# stack_4.net
KiCad netlist of a schematic drawn in EAGLE
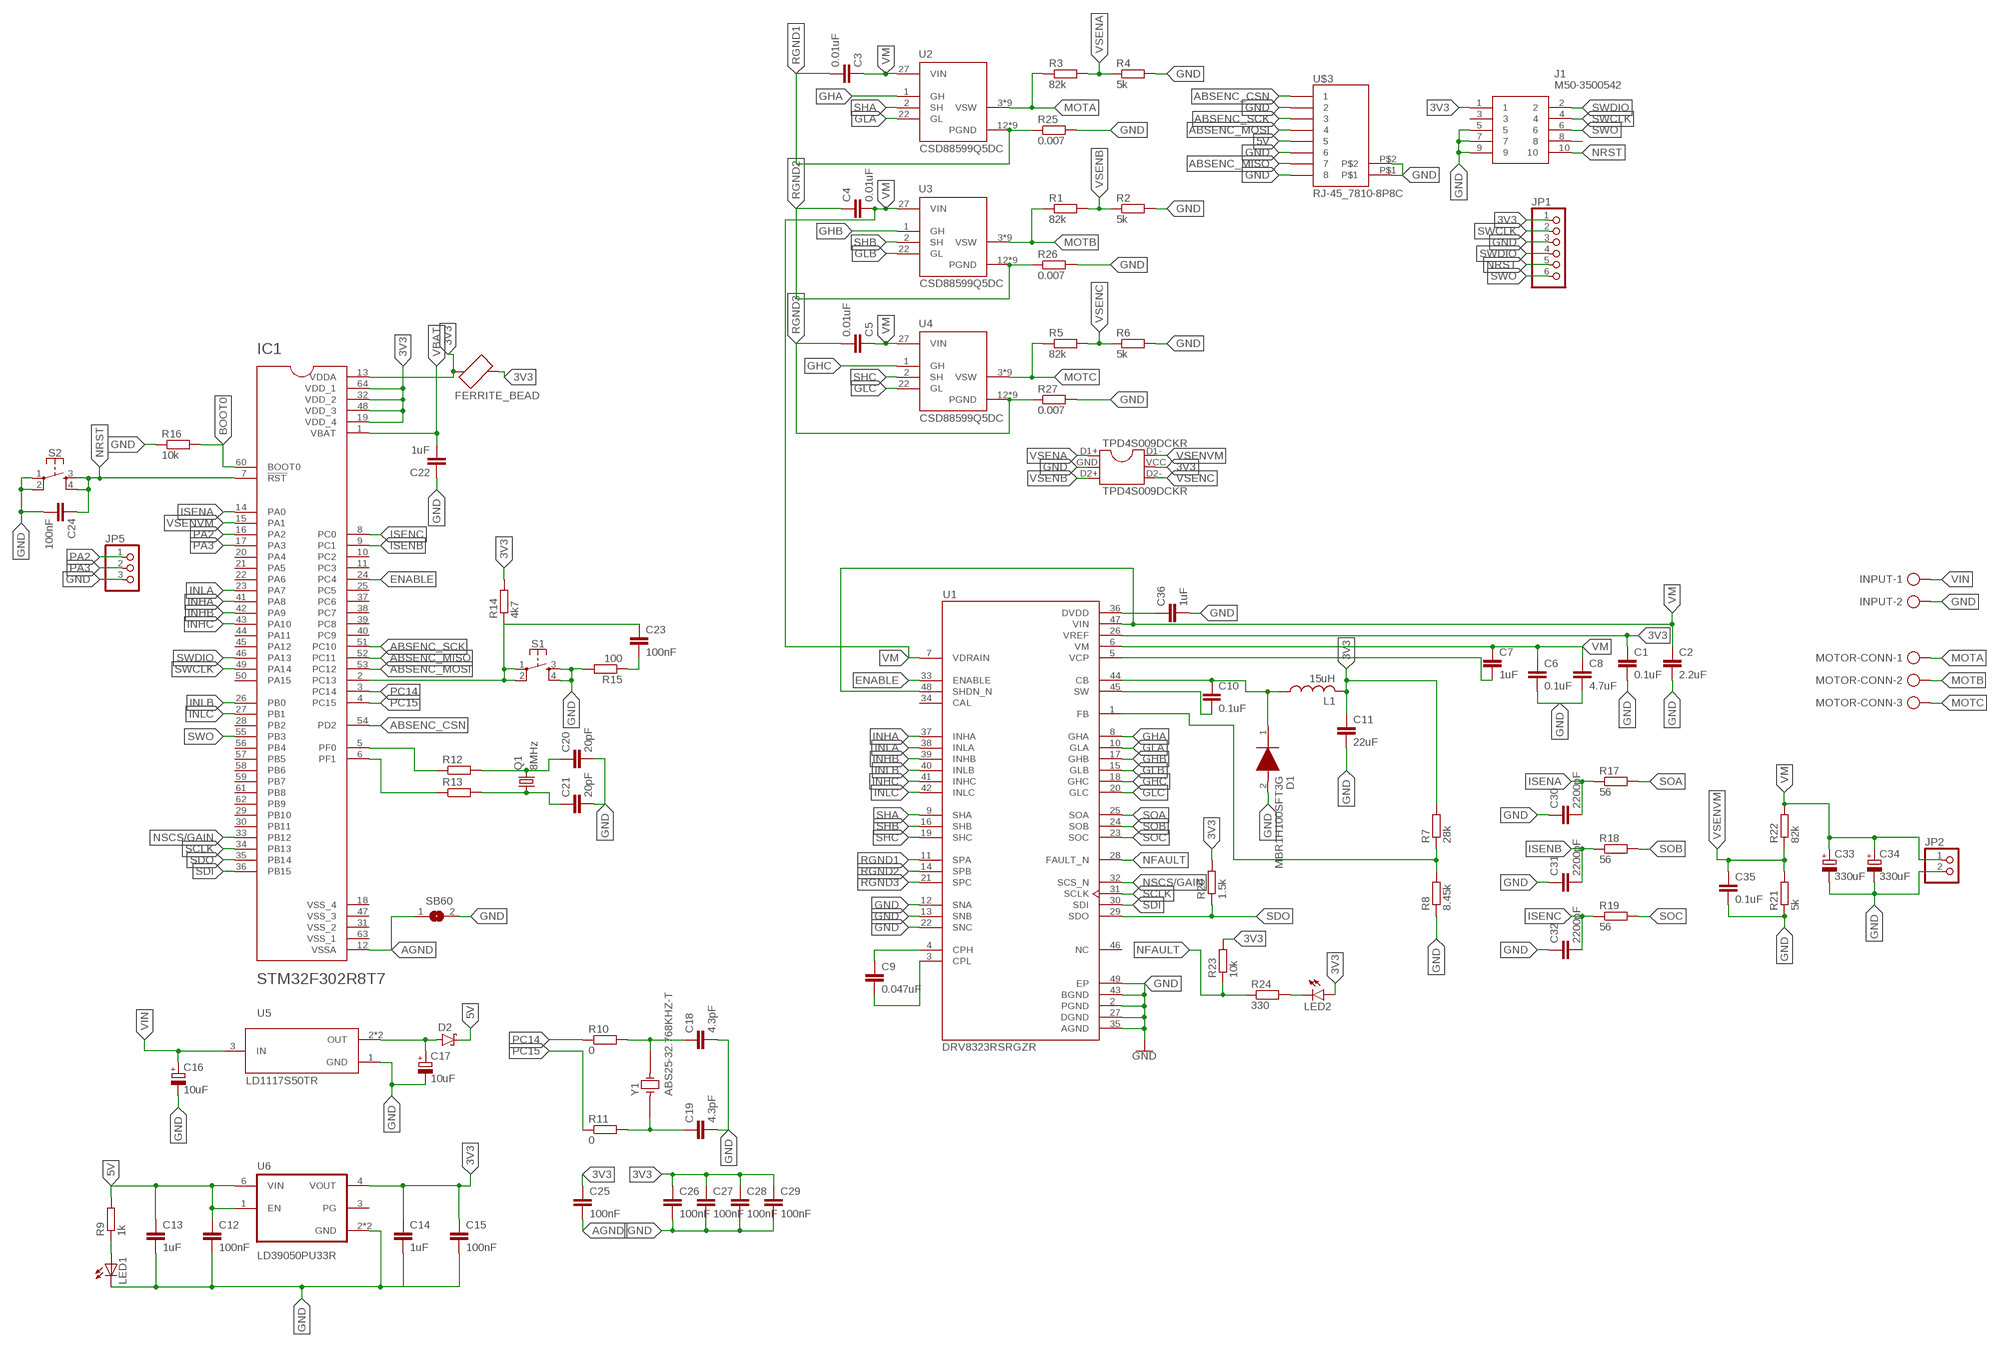
[diagram p0: schematic, sheet 1]

(export (version "E")
  (design (tool "Eeschema 10.0.6"))
  (components
    (comp (ref "C1")
      (value "0.1uF")
      (footprint "eagle-import:C1206")
      (libsource (lib "eagle-import") (part "C-EUC1206"))
    )
    (comp (ref "C2")
      (value "2.2uF")
      (footprint "eagle-import:C0805")
      (libsource (lib "eagle-import") (part "C-EUC0805"))
    )
    (comp (ref "C3")
      (value "0.01uF")
      (footprint "eagle-import:C0805")
      (libsource (lib "eagle-import") (part "C-EUC0805"))
    )
    (comp (ref "C4")
      (value "0.01uF")
      (footprint "eagle-import:C0805")
      (libsource (lib "eagle-import") (part "C-EUC0805"))
    )
    (comp (ref "C5")
      (value "0.01uF")
      (footprint "eagle-import:C0805")
      (libsource (lib "eagle-import") (part "C-EUC0805"))
    )
    (comp (ref "C6")
      (value "0.1uF")
      (footprint "eagle-import:C1206")
      (libsource (lib "eagle-import") (part "C-EUC1206"))
    )
    (comp (ref "C7")
      (value "1uF")
      (footprint "eagle-import:C1206")
      (libsource (lib "eagle-import") (part "C-EUC1206"))
    )
    (comp (ref "C8")
      (value "4.7uF")
      (footprint "eagle-import:C1206")
      (libsource (lib "eagle-import") (part "C-EUC1206"))
    )
    (comp (ref "C9")
      (value "0.047uF")
      (footprint "eagle-import:C0603")
      (libsource (lib "eagle-import") (part "C-EUC0603"))
    )
    (comp (ref "C10")
      (value "0.1uF")
      (footprint "eagle-import:C1206")
      (libsource (lib "eagle-import") (part "C-EUC1206"))
    )
    (comp (ref "C11")
      (value "22uF")
      (footprint "eagle-import:C1206")
      (libsource (lib "eagle-import") (part "C-EUC1206"))
    )
    (comp (ref "C12")
      (value "100nF")
      (footprint "eagle-import:C1206")
      (libsource (lib "eagle-import") (part "C-EUC1206"))
    )
    (comp (ref "C13")
      (value "1uF")
      (footprint "eagle-import:C0603")
      (libsource (lib "eagle-import") (part "C-EUC0603"))
    )
    (comp (ref "C14")
      (value "1uF")
      (footprint "eagle-import:C0603")
      (libsource (lib "eagle-import") (part "C-EUC0603"))
    )
    (comp (ref "C15")
      (value "100nF")
      (footprint "eagle-import:C1206")
      (libsource (lib "eagle-import") (part "C-EUC1206"))
    )
    (comp (ref "C16")
      (value "10uF")
      (footprint "eagle-import:UD-6,3X5,8_NICHICON")
      (libsource (lib "eagle-import") (part "CPOL-EUUD-6,3X8,8"))
    )
    (comp (ref "C17")
      (value "10uF")
      (footprint "eagle-import:UD-6,3X5,8_NICHICON")
      (libsource (lib "eagle-import") (part "CPOL-EUUD-6,3X8,8"))
    )
    (comp (ref "C18")
      (value "4.3pF")
      (footprint "eagle-import:C025-024X044")
      (libsource (lib "eagle-import") (part "C-EU025-024X044"))
    )
    (comp (ref "C19")
      (value "4.3pF")
      (footprint "eagle-import:C025-024X044")
      (libsource (lib "eagle-import") (part "C-EU025-024X044"))
    )
    (comp (ref "C20")
      (value "20pF")
      (footprint "eagle-import:C025-024X044")
      (libsource (lib "eagle-import") (part "C-EU025-024X044"))
    )
    (comp (ref "C21")
      (value "20pF")
      (footprint "eagle-import:C025-024X044")
      (libsource (lib "eagle-import") (part "C-EU025-024X044"))
    )
    (comp (ref "C22")
      (value "1uF")
      (footprint "eagle-import:C0805")
      (libsource (lib "eagle-import") (part "C-EUC0805"))
    )
    (comp (ref "C23")
      (value "100nF")
      (footprint "eagle-import:C0805")
      (libsource (lib "eagle-import") (part "C-EUC0805"))
    )
    (comp (ref "C24")
      (value "100nF")
      (footprint "eagle-import:C0805")
      (libsource (lib "eagle-import") (part "C-EUC0805"))
    )
    (comp (ref "C25")
      (value "100nF")
      (footprint "eagle-import:C0805")
      (libsource (lib "eagle-import") (part "C-EUC0805"))
    )
    (comp (ref "C26")
      (value "100nF")
      (footprint "eagle-import:C0805")
      (libsource (lib "eagle-import") (part "C-EUC0805"))
    )
    (comp (ref "C27")
      (value "100nF")
      (footprint "eagle-import:C0805")
      (libsource (lib "eagle-import") (part "C-EUC0805"))
    )
    (comp (ref "C28")
      (value "100nF")
      (footprint "eagle-import:C0805")
      (libsource (lib "eagle-import") (part "C-EUC0805"))
    )
    (comp (ref "C29")
      (value "100nF")
      (footprint "eagle-import:C0805")
      (libsource (lib "eagle-import") (part "C-EUC0805"))
    )
    (comp (ref "C30")
      (value "2200pF")
      (footprint "eagle-import:C0603")
      (libsource (lib "eagle-import") (part "C-EUC0603"))
    )
    (comp (ref "C31")
      (value "2200pF")
      (footprint "eagle-import:C0603")
      (libsource (lib "eagle-import") (part "C-EUC0603"))
    )
    (comp (ref "C32")
      (value "2200pF")
      (footprint "eagle-import:C0603")
      (libsource (lib "eagle-import") (part "C-EUC0603"))
    )
    (comp (ref "C33")
      (value "330uF")
      (footprint "eagle-import:UD-10X10_NICHICON")
      (libsource (lib "eagle-import") (part "CPOL-EUUD-10X10"))
    )
    (comp (ref "C34")
      (value "330uF")
      (footprint "eagle-import:UD-10X10_NICHICON")
      (libsource (lib "eagle-import") (part "CPOL-EUUD-10X10"))
    )
    (comp (ref "C35")
      (value "0.1uF")
      (footprint "eagle-import:C1206")
      (libsource (lib "eagle-import") (part "C-EUC1206"))
    )
    (comp (ref "C36")
      (value "1uF")
      (footprint "eagle-import:C1206")
      (libsource (lib "eagle-import") (part "C-EUC1206"))
    )
    (comp (ref "D1")
      (value "MBR1H100SFT3G")
      (footprint "eagle-import:SODFL3616X98N")
      (fields (field (name "MOUSER_PART_NUMBER") "863-MBR1H100SFT3G"))
      (libsource (lib "eagle-import") (part "MBR1H100SFT3G"))
    )
    (comp (ref "D2")
      (value "SCHOTTKY-DIODESMD")
      (footprint "eagle-import:SMB")
      (libsource (lib "eagle-import") (part "SCHOTTKY-DIODESMD"))
    )
    (comp (ref "IC1")
      (value "STM32F302R8T7")
      (footprint "eagle-import:QFP50P1200X1200X160-64N")
      (fields (field (name "MF") "STMicroelectronics"))
      (libsource (lib "eagle-import") (part "STM32F302R8T7"))
    )
    (comp (ref "INPUT")
      (value "AK500/2-H")
      (footprint "eagle-import:AK500_2-H")
      (libsource (lib "eagle-import") (part "AK500/2-H"))
    )
    (comp (ref "J1")
      (value "M50-3500542")
      (footprint "eagle-import:M503500542")
      (fields
        (field (name "MOUSER_PART_NUMBER") "855-M50-3500542")
        (field (name "RS_PART_NUMBER") "6811184P")
      )
      (libsource (lib "eagle-import") (part "M50-3500542"))
    )
    (comp (ref "JP1")
      (value "PINHD-1X6")
      (footprint "eagle-import:1X06")
      (libsource (lib "eagle-import") (part "PINHD-1X6"))
    )
    (comp (ref "JP2")
      (value "PINHD-1X2")
      (footprint "eagle-import:1X02")
      (libsource (lib "eagle-import") (part "PINHD-1X2"))
    )
    (comp (ref "JP5")
      (value "PINHD-1X3")
      (footprint "eagle-import:1X03")
      (libsource (lib "eagle-import") (part "PINHD-1X3"))
    )
    (comp (ref "L1")
      (value "15uH")
      (footprint "eagle-import:0805")
      (libsource (lib "eagle-import") (part "L_0805"))
    )
    (comp (ref "LED1")
      (value "LEDCHIP-LED0603")
      (footprint "eagle-import:CHIP-LED0603")
      (libsource (lib "eagle-import") (part "LEDCHIP-LED0603"))
    )
    (comp (ref "LED2")
      (value "LEDSML0805")
      (footprint "eagle-import:SML0805")
      (libsource (lib "eagle-import") (part "LEDSML0805"))
    )
    (comp (ref "MOTOR-CONN")
      (value "AK500/3-H")
      (footprint "eagle-import:AK500_3-H")
      (libsource (lib "eagle-import") (part "AK500/3-H"))
    )
    (comp (ref "Q1")
      (value "8MHz")
      (footprint "eagle-import:HC49UP")
      (libsource (lib "eagle-import") (part "CRYSTALHC49UP"))
    )
    (comp (ref "R1")
      (value "82k")
      (footprint "eagle-import:R0805")
      (libsource (lib "eagle-import") (part "R-EU_R0805"))
    )
    (comp (ref "R2")
      (value "5k")
      (footprint "eagle-import:R0603")
      (libsource (lib "eagle-import") (part "R-EU_R0603"))
    )
    (comp (ref "R3")
      (value "82k")
      (footprint "eagle-import:R0805")
      (libsource (lib "eagle-import") (part "R-EU_R0805"))
    )
    (comp (ref "R4")
      (value "5k")
      (footprint "eagle-import:R0603")
      (libsource (lib "eagle-import") (part "R-EU_R0603"))
    )
    (comp (ref "R5")
      (value "82k")
      (footprint "eagle-import:R0805")
      (libsource (lib "eagle-import") (part "R-EU_R0805"))
    )
    (comp (ref "R6")
      (value "5k")
      (footprint "eagle-import:R0603")
      (libsource (lib "eagle-import") (part "R-EU_R0603"))
    )
    (comp (ref "R7")
      (value "28k")
      (footprint "eagle-import:R0805")
      (libsource (lib "eagle-import") (part "R-EU_R0805"))
    )
    (comp (ref "R8")
      (value "8.45k")
      (footprint "eagle-import:R0805")
      (libsource (lib "eagle-import") (part "R-EU_R0805"))
    )
    (comp (ref "R9")
      (value "1k")
      (footprint "eagle-import:R0805")
      (libsource (lib "eagle-import") (part "R-EU_R0805"))
    )
    (comp (ref "R10")
      (value "0")
      (footprint "eagle-import:R0805")
      (libsource (lib "eagle-import") (part "R-EU_R0805"))
    )
    (comp (ref "R11")
      (value "0")
      (footprint "eagle-import:R0805")
      (libsource (lib "eagle-import") (part "R-EU_R0805"))
    )
    (comp (ref "R12")
      (value "R-EU_R0805")
      (footprint "eagle-import:R0805")
      (libsource (lib "eagle-import") (part "R-EU_R0805"))
    )
    (comp (ref "R13")
      (value "R-EU_R0805")
      (footprint "eagle-import:R0805")
      (libsource (lib "eagle-import") (part "R-EU_R0805"))
    )
    (comp (ref "R14")
      (value "4k7")
      (footprint "eagle-import:R0805")
      (libsource (lib "eagle-import") (part "R-EU_R0805"))
    )
    (comp (ref "R15")
      (value "100")
      (footprint "eagle-import:R0805")
      (libsource (lib "eagle-import") (part "R-EU_R0805"))
    )
    (comp (ref "R16")
      (value "10k")
      (footprint "eagle-import:R0805")
      (libsource (lib "eagle-import") (part "R-EU_R0805"))
    )
    (comp (ref "R17")
      (value "56")
      (footprint "eagle-import:R0603")
      (libsource (lib "eagle-import") (part "R-EU_R0603"))
    )
    (comp (ref "R18")
      (value "56")
      (footprint "eagle-import:R0603")
      (libsource (lib "eagle-import") (part "R-EU_R0603"))
    )
    (comp (ref "R19")
      (value "56")
      (footprint "eagle-import:R0603")
      (libsource (lib "eagle-import") (part "R-EU_R0603"))
    )
    (comp (ref "R20")
      (value "1.5k")
      (footprint "eagle-import:R0805")
      (libsource (lib "eagle-import") (part "R-EU_R0805"))
    )
    (comp (ref "R21")
      (value "5k")
      (footprint "eagle-import:R0603")
      (libsource (lib "eagle-import") (part "R-EU_R0603"))
    )
    (comp (ref "R22")
      (value "82k")
      (footprint "eagle-import:R0805")
      (libsource (lib "eagle-import") (part "R-EU_R0805"))
    )
    (comp (ref "R23")
      (value "10k")
      (footprint "eagle-import:R0805")
      (libsource (lib "eagle-import") (part "R-EU_R0805"))
    )
    (comp (ref "R24")
      (value "330")
      (footprint "eagle-import:R0805")
      (libsource (lib "eagle-import") (part "R-EU_R0805"))
    )
    (comp (ref "R25")
      (value "0.007")
      (footprint "eagle-import:R2512")
      (libsource (lib "eagle-import") (part "R-EU_R2512"))
    )
    (comp (ref "R26")
      (value "0.007")
      (footprint "eagle-import:R2512")
      (libsource (lib "eagle-import") (part "R-EU_R2512"))
    )
    (comp (ref "R27")
      (value "0.007")
      (footprint "eagle-import:R2512")
      (libsource (lib "eagle-import") (part "R-EU_R2512"))
    )
    (comp (ref "S1")
      (value "MOMENTARY-SWITCH-SPST-2-SMD-5.2MM")
      (footprint "eagle-import:TACTILE_SWITCH_SMD_5.2MM")
      (libsource (lib "eagle-import") (part "MOMENTARY-SWITCH-SPST-2-SMD-5.2MM"))
    )
    (comp (ref "S2")
      (value "MOMENTARY-SWITCH-SPST-2-SMD-5.2MM")
      (footprint "eagle-import:TACTILE_SWITCH_SMD_5.2MM")
      (libsource (lib "eagle-import") (part "MOMENTARY-SWITCH-SPST-2-SMD-5.2MM"))
    )
    (comp (ref "SB60")
      (value "SJW")
      (footprint "eagle-import:SJW")
      (libsource (lib "eagle-import") (part "SJW"))
    )
    (comp (ref "U$1")
      (value "TPD4S009DCKR")
      (footprint "eagle-import:TPD4S009DCKR")
      (libsource (lib "eagle-import") (part "TPD4S009DCKR"))
    )
    (comp (ref "U$2")
      (value "FERRITE_BEAD")
      (footprint "eagle-import:RESC0603X26N")
      (libsource (lib "eagle-import") (part "FERRITE_BEAD"))
    )
    (comp (ref "U$3")
      (value "RJ-45_7810-8P8C")
      (footprint "eagle-import:RJ-45_7810-8P8C")
      (libsource (lib "eagle-import") (part "RJ-45_7810-8P8C"))
    )
    (comp (ref "U1")
      (value "DRV8323RSRGZR")
      (footprint "eagle-import:QFN50P700X700X100-49N")
      (fields (field (name "MF") "Texas Instruments"))
      (libsource (lib "eagle-import") (part "DRV8323RSRGZR"))
    )
    (comp (ref "U2")
      (value "CSD88599Q5DC")
      (footprint "eagle-import:MOSFET_CSD88599Q5DC")
      (fields (field (name "MF") "Texas Instruments"))
      (libsource (lib "eagle-import") (part "CSD88599Q5DC"))
    )
    (comp (ref "U3")
      (value "CSD88599Q5DC")
      (footprint "eagle-import:MOSFET_CSD88599Q5DC")
      (fields (field (name "MF") "Texas Instruments"))
      (libsource (lib "eagle-import") (part "CSD88599Q5DC"))
    )
    (comp (ref "U4")
      (value "CSD88599Q5DC")
      (footprint "eagle-import:MOSFET_CSD88599Q5DC")
      (fields (field (name "MF") "Texas Instruments"))
      (libsource (lib "eagle-import") (part "CSD88599Q5DC"))
    )
    (comp (ref "U5")
      (value "LD1117S50TR")
      (footprint "eagle-import:SOT230P700X180-4N")
      (fields (field (name "MF") "STMicroelectronics"))
      (libsource (lib "eagle-import") (part "LD1117S50TR"))
    )
    (comp (ref "U6")
      (value "LD39050PU33R")
      (footprint "eagle-import:SON95P300X300X100-7N")
      (fields (field (name "MF") "STMicroelectronics"))
      (libsource (lib "eagle-import") (part "LD39050PU33R"))
    )
    (comp (ref "Y1")
      (value "ABS25-32.768KHZ-T")
      (footprint "eagle-import:XTAL_ABS25-32.768KHZ-6-1-T")
      (fields (field (name "MF") "Abracon"))
      (libsource (lib "eagle-import") (part "ABS25-32.768KHZ-T"))
    )
  )
  (nets
    (net (code "1") (name "3V3") (class "Default")
      (node (ref "C1") (pin "1") (pinfunction "1_1") (pintype "passive"))
      (node (ref "C11") (pin "1") (pinfunction "1_1") (pintype "passive"))
      (node (ref "C14") (pin "1") (pinfunction "1_1") (pintype "passive"))
      (node (ref "C15") (pin "1") (pinfunction "1_1") (pintype "passive"))
      (node (ref "C25") (pin "1") (pinfunction "1_1") (pintype "passive"))
      (node (ref "C26") (pin "1") (pinfunction "1_1") (pintype "passive"))
      (node (ref "C27") (pin "1") (pinfunction "1_1") (pintype "passive"))
      (node (ref "C28") (pin "1") (pinfunction "1_1") (pintype "passive"))
      (node (ref "C29") (pin "1") (pinfunction "1_1") (pintype "passive"))
      (node (ref "IC1") (pin "13") (pinfunction "VDDA_13") (pintype "power_in"))
      (node (ref "IC1") (pin "19") (pinfunction "VDD_4_19") (pintype "power_in"))
      (node (ref "IC1") (pin "32") (pinfunction "VDD_2_32") (pintype "power_in"))
      (node (ref "IC1") (pin "48") (pinfunction "VDD_3_48") (pintype "power_in"))
      (node (ref "IC1") (pin "64") (pinfunction "VDD_1_64") (pintype "power_in"))
      (node (ref "J1") (pin "1") (pinfunction "1_1") (pintype "bidirectional"))
      (node (ref "JP1") (pin "1") (pinfunction "1_1") (pintype "passive"))
      (node (ref "L1") (pin "2") (pinfunction "2_2") (pintype "passive"))
      (node (ref "LED2") (pin "A") (pinfunction "A_A") (pintype "passive"))
      (node (ref "R14") (pin "2") (pinfunction "2_2") (pintype "passive"))
      (node (ref "R20") (pin "2") (pinfunction "2_2") (pintype "passive"))
      (node (ref "R23") (pin "2") (pinfunction "2_2") (pintype "passive"))
      (node (ref "R7") (pin "2") (pinfunction "2_2") (pintype "passive"))
      (node (ref "U$1") (pin "VCC") (pinfunction "VCC_VCC") (pintype "passive"))
      (node (ref "U$2") (pin "1") (pinfunction "P$1_1") (pintype "bidirectional"))
      (node (ref "U$2") (pin "2") (pinfunction "P$3_2") (pintype "bidirectional"))
      (node (ref "U1") (pin "26") (pinfunction "VREF_26") (pintype "power_in"))
      (node (ref "U6") (pin "4") (pinfunction "VOUT_4") (pintype "output"))
    )
    (net (code "2") (name "5V") (class "Default")
      (node (ref "C12") (pin "1") (pinfunction "1_1") (pintype "passive"))
      (node (ref "C13") (pin "1") (pinfunction "1_1") (pintype "passive"))
      (node (ref "D2") (pin "C") (pinfunction "C_C") (pintype "passive"))
      (node (ref "R9") (pin "2") (pinfunction "2_2") (pintype "passive"))
      (node (ref "U$3") (pin "5") (pinfunction "5_5") (pintype "bidirectional"))
      (node (ref "U6") (pin "1") (pinfunction "EN_1") (pintype "input"))
      (node (ref "U6") (pin "6") (pinfunction "VIN_6") (pintype "power_in"))
    )
    (net (code "3") (name "ABSENC_CSN") (class "Default")
      (node (ref "IC1") (pin "54") (pinfunction "PD2_54") (pintype "bidirectional"))
      (node (ref "U$3") (pin "1") (pinfunction "1_1") (pintype "bidirectional"))
    )
    (net (code "4") (name "ABSENC_MISO") (class "Default")
      (node (ref "IC1") (pin "52") (pinfunction "PC11_52") (pintype "bidirectional"))
      (node (ref "U$3") (pin "7") (pinfunction "7_7") (pintype "bidirectional"))
    )
    (net (code "5") (name "ABSENC_MOSI") (class "Default")
      (node (ref "IC1") (pin "53") (pinfunction "PC12_53") (pintype "bidirectional"))
      (node (ref "U$3") (pin "4") (pinfunction "4_4") (pintype "bidirectional"))
    )
    (net (code "6") (name "ABSENC_SCK") (class "Default")
      (node (ref "IC1") (pin "51") (pinfunction "PC10_51") (pintype "bidirectional"))
      (node (ref "U$3") (pin "3") (pinfunction "3_3") (pintype "bidirectional"))
    )
    (net (code "7") (name "AGND") (class "Default")
      (node (ref "C25") (pin "2") (pinfunction "2_2") (pintype "passive"))
      (node (ref "IC1") (pin "12") (pinfunction "VSSA_12") (pintype "passive"))
      (node (ref "SB60") (pin "1") (pinfunction "1_1") (pintype "passive"))
    )
    (net (code "8") (name "BOOT0") (class "Default")
      (node (ref "IC1") (pin "60") (pinfunction "BOOT0_60") (pintype "input"))
      (node (ref "R16") (pin "2") (pinfunction "2_2") (pintype "passive"))
    )
    (net (code "9") (name "ENABLE") (class "Default")
      (node (ref "IC1") (pin "24") (pinfunction "PC4_24") (pintype "bidirectional"))
      (node (ref "U1") (pin "33") (pinfunction "ENABLE_33") (pintype "input"))
    )
    (net (code "10") (name "GHA") (class "Default")
      (node (ref "U1") (pin "8") (pinfunction "GHA_8") (pintype "output"))
      (node (ref "U2") (pin "1") (pinfunction "GH_1") (pintype "input"))
    )
    (net (code "11") (name "GHB") (class "Default")
      (node (ref "U1") (pin "17") (pinfunction "GHB_17") (pintype "output"))
      (node (ref "U3") (pin "1") (pinfunction "GH_1") (pintype "input"))
    )
    (net (code "12") (name "GHC") (class "Default")
      (node (ref "U1") (pin "18") (pinfunction "GHC_18") (pintype "output"))
      (node (ref "U4") (pin "1") (pinfunction "GH_1") (pintype "input"))
    )
    (net (code "13") (name "GLA") (class "Default")
      (node (ref "U1") (pin "10") (pinfunction "GLA_10") (pintype "output"))
      (node (ref "U2") (pin "22") (pinfunction "GL_22") (pintype "input"))
    )
    (net (code "14") (name "GLB") (class "Default")
      (node (ref "U1") (pin "15") (pinfunction "GLB_15") (pintype "output"))
      (node (ref "U3") (pin "22") (pinfunction "GL_22") (pintype "input"))
    )
    (net (code "15") (name "GLC") (class "Default")
      (node (ref "U1") (pin "20") (pinfunction "GLC_20") (pintype "output"))
      (node (ref "U4") (pin "22") (pinfunction "GL_22") (pintype "input"))
    )
    (net (code "16") (name "GND") (class "Default")
      (node (ref "C1") (pin "2") (pinfunction "2_2") (pintype "passive"))
      (node (ref "C11") (pin "2") (pinfunction "2_2") (pintype "passive"))
      (node (ref "C12") (pin "2") (pinfunction "2_2") (pintype "passive"))
      (node (ref "C13") (pin "2") (pinfunction "2_2") (pintype "passive"))
      (node (ref "C14") (pin "2") (pinfunction "2_2") (pintype "passive"))
      (node (ref "C15") (pin "2") (pinfunction "2_2") (pintype "passive"))
      (node (ref "C16") (pin "-") (pinfunction "-_-") (pintype "passive"))
      (node (ref "C17") (pin "-") (pinfunction "-_-") (pintype "passive"))
      (node (ref "C18") (pin "2") (pinfunction "2_2") (pintype "passive"))
      (node (ref "C19") (pin "2") (pinfunction "2_2") (pintype "passive"))
      (node (ref "C2") (pin "2") (pinfunction "2_2") (pintype "passive"))
      (node (ref "C20") (pin "2") (pinfunction "2_2") (pintype "passive"))
      (node (ref "C21") (pin "2") (pinfunction "2_2") (pintype "passive"))
      (node (ref "C22") (pin "1") (pinfunction "1_1") (pintype "passive"))
      (node (ref "C24") (pin "2") (pinfunction "2_2") (pintype "passive"))
      (node (ref "C26") (pin "2") (pinfunction "2_2") (pintype "passive"))
      (node (ref "C27") (pin "2") (pinfunction "2_2") (pintype "passive"))
      (node (ref "C28") (pin "2") (pinfunction "2_2") (pintype "passive"))
      (node (ref "C29") (pin "2") (pinfunction "2_2") (pintype "passive"))
      (node (ref "C30") (pin "1") (pinfunction "1_1") (pintype "passive"))
      (node (ref "C31") (pin "1") (pinfunction "1_1") (pintype "passive"))
      (node (ref "C32") (pin "1") (pinfunction "1_1") (pintype "passive"))
      (node (ref "C33") (pin "-") (pinfunction "-_-") (pintype "passive"))
      (node (ref "C34") (pin "-") (pinfunction "-_-") (pintype "passive"))
      (node (ref "C35") (pin "2") (pinfunction "2_2") (pintype "passive"))
      (node (ref "C36") (pin "2") (pinfunction "2_2") (pintype "passive"))
      (node (ref "C6") (pin "2") (pinfunction "2_2") (pintype "passive"))
      (node (ref "C8") (pin "2") (pinfunction "2_2") (pintype "passive"))
      (node (ref "D1") (pin "2") (pinfunction "A_2") (pintype "bidirectional"))
      (node (ref "INPUT") (pin "2") (pinfunction "KL_2") (pintype "passive"))
      (node (ref "J1") (pin "5") (pinfunction "5_5") (pintype "bidirectional"))
      (node (ref "J1") (pin "7") (pinfunction "7_7") (pintype "bidirectional"))
      (node (ref "J1") (pin "9") (pinfunction "9_9") (pintype "bidirectional"))
      (node (ref "JP1") (pin "3") (pinfunction "3_3") (pintype "passive"))
      (node (ref "JP2") (pin "2") (pinfunction "2_2") (pintype "passive"))
      (node (ref "JP5") (pin "3") (pinfunction "3_3") (pintype "passive"))
      (node (ref "LED1") (pin "C") (pinfunction "C_C") (pintype "passive"))
      (node (ref "R15") (pin "2") (pinfunction "2_2") (pintype "passive"))
      (node (ref "R16") (pin "1") (pinfunction "1_1") (pintype "passive"))
      (node (ref "R2") (pin "2") (pinfunction "2_2") (pintype "passive"))
      (node (ref "R21") (pin "1") (pinfunction "1_1") (pintype "passive"))
      (node (ref "R25") (pin "2") (pinfunction "2_2") (pintype "passive"))
      (node (ref "R26") (pin "2") (pinfunction "2_2") (pintype "passive"))
      (node (ref "R27") (pin "2") (pinfunction "2_2") (pintype "passive"))
      (node (ref "R4") (pin "2") (pinfunction "2_2") (pintype "passive"))
      (node (ref "R6") (pin "2") (pinfunction "2_2") (pintype "passive"))
      (node (ref "R8") (pin "1") (pinfunction "1_1") (pintype "passive"))
      (node (ref "S1") (pin "3") (pinfunction "3_3") (pintype "passive"))
      (node (ref "S1") (pin "4") (pinfunction "4_4") (pintype "passive"))
      (node (ref "S2") (pin "1") (pinfunction "1_1") (pintype "passive"))
      (node (ref "S2") (pin "2") (pinfunction "2_2") (pintype "passive"))
      (node (ref "SB60") (pin "2") (pinfunction "2_2") (pintype "passive"))
      (node (ref "U$1") (pin "GND") (pinfunction "GND_GND") (pintype "passive"))
      (node (ref "U$3") (pin "2") (pinfunction "2_2") (pintype "bidirectional"))
      (node (ref "U$3") (pin "6") (pinfunction "6_6") (pintype "bidirectional"))
      (node (ref "U$3") (pin "8") (pinfunction "8_8") (pintype "bidirectional"))
      (node (ref "U$3") (pin "P$1") (pinfunction "P$1_P$1") (pintype "bidirectional"))
      (node (ref "U$3") (pin "P$2") (pinfunction "P$2_P$2") (pintype "bidirectional"))
      (node (ref "U1") (pin "12") (pinfunction "SNA_12") (pintype "input"))
      (node (ref "U1") (pin "13") (pinfunction "SNB_13") (pintype "input"))
      (node (ref "U1") (pin "2") (pinfunction "PGND_2") (pintype "power_in"))
      (node (ref "U1") (pin "22") (pinfunction "SNC_22") (pintype "input"))
      (node (ref "U1") (pin "27") (pinfunction "DGND_27") (pintype "power_in"))
      (node (ref "U1") (pin "35") (pinfunction "AGND_35") (pintype "power_in"))
      (node (ref "U1") (pin "43") (pinfunction "BGND_43") (pintype "power_in"))
      (node (ref "U1") (pin "49") (pinfunction "EP_49") (pintype "power_in"))
      (node (ref "U5") (pin "1") (pinfunction "GND_1") (pintype "power_in"))
      (node (ref "U6") (pin "2") (pinfunction "GND_2") (pintype "power_in"))
      (node (ref "U6") (pin "7") (pinfunction "GND_7") (pintype "power_in"))
    )
    (net (code "17") (name "INHA") (class "Default")
      (node (ref "IC1") (pin "41") (pinfunction "PA8_41") (pintype "bidirectional"))
      (node (ref "U1") (pin "37") (pinfunction "INHA_37") (pintype "input"))
    )
    (net (code "18") (name "INHB") (class "Default")
      (node (ref "IC1") (pin "42") (pinfunction "PA9_42") (pintype "bidirectional"))
      (node (ref "U1") (pin "39") (pinfunction "INHB_39") (pintype "input"))
    )
    (net (code "19") (name "INHC") (class "Default")
      (node (ref "IC1") (pin "43") (pinfunction "PA10_43") (pintype "bidirectional"))
      (node (ref "U1") (pin "41") (pinfunction "INHC_41") (pintype "input"))
    )
    (net (code "20") (name "INLA") (class "Default")
      (node (ref "IC1") (pin "23") (pinfunction "PA7_23") (pintype "bidirectional"))
      (node (ref "U1") (pin "38") (pinfunction "INLA_38") (pintype "input"))
    )
    (net (code "21") (name "INLB") (class "Default")
      (node (ref "IC1") (pin "26") (pinfunction "PB0_26") (pintype "bidirectional"))
      (node (ref "U1") (pin "40") (pinfunction "INLB_40") (pintype "input"))
    )
    (net (code "22") (name "INLC") (class "Default")
      (node (ref "IC1") (pin "27") (pinfunction "PB1_27") (pintype "bidirectional"))
      (node (ref "U1") (pin "42") (pinfunction "INLC_42") (pintype "input"))
    )
    (net (code "23") (name "ISENA") (class "Default")
      (node (ref "C30") (pin "2") (pinfunction "2_2") (pintype "passive"))
      (node (ref "IC1") (pin "14") (pinfunction "PA0_14") (pintype "bidirectional"))
      (node (ref "R17") (pin "1") (pinfunction "1_1") (pintype "passive"))
    )
    (net (code "24") (name "ISENB") (class "Default")
      (node (ref "C31") (pin "2") (pinfunction "2_2") (pintype "passive"))
      (node (ref "IC1") (pin "9") (pinfunction "PC1_9") (pintype "bidirectional"))
      (node (ref "R18") (pin "1") (pinfunction "1_1") (pintype "passive"))
    )
    (net (code "25") (name "ISENC") (class "Default")
      (node (ref "C32") (pin "2") (pinfunction "2_2") (pintype "passive"))
      (node (ref "IC1") (pin "8") (pinfunction "PC0_8") (pintype "bidirectional"))
      (node (ref "R19") (pin "1") (pinfunction "1_1") (pintype "passive"))
    )
    (net (code "26") (name "MOTA") (class "Default")
      (node (ref "MOTOR-CONN") (pin "1") (pinfunction "KL_1") (pintype "passive"))
      (node (ref "R3") (pin "1") (pinfunction "1_1") (pintype "passive"))
      (node (ref "U2") (pin "10") (pinfunction "VSW_10") (pintype "output"))
      (node (ref "U2") (pin "11") (pinfunction "VSW_11") (pintype "output"))
      (node (ref "U2") (pin "3") (pinfunction "VSW_3") (pintype "output"))
      (node (ref "U2") (pin "4") (pinfunction "VSW_4") (pintype "output"))
      (node (ref "U2") (pin "5") (pinfunction "VSW_5") (pintype "output"))
      (node (ref "U2") (pin "6") (pinfunction "VSW_6") (pintype "output"))
      (node (ref "U2") (pin "7") (pinfunction "VSW_7") (pintype "output"))
      (node (ref "U2") (pin "8") (pinfunction "VSW_8") (pintype "output"))
      (node (ref "U2") (pin "9") (pinfunction "VSW_9") (pintype "output"))
    )
    (net (code "27") (name "MOTB") (class "Default")
      (node (ref "MOTOR-CONN") (pin "2") (pinfunction "KL_2") (pintype "passive"))
      (node (ref "R1") (pin "1") (pinfunction "1_1") (pintype "passive"))
      (node (ref "U3") (pin "10") (pinfunction "VSW_10") (pintype "output"))
      (node (ref "U3") (pin "11") (pinfunction "VSW_11") (pintype "output"))
      (node (ref "U3") (pin "3") (pinfunction "VSW_3") (pintype "output"))
      (node (ref "U3") (pin "4") (pinfunction "VSW_4") (pintype "output"))
      (node (ref "U3") (pin "5") (pinfunction "VSW_5") (pintype "output"))
      (node (ref "U3") (pin "6") (pinfunction "VSW_6") (pintype "output"))
      (node (ref "U3") (pin "7") (pinfunction "VSW_7") (pintype "output"))
      (node (ref "U3") (pin "8") (pinfunction "VSW_8") (pintype "output"))
      (node (ref "U3") (pin "9") (pinfunction "VSW_9") (pintype "output"))
    )
    (net (code "28") (name "MOTC") (class "Default")
      (node (ref "MOTOR-CONN") (pin "3") (pinfunction "KL_3") (pintype "passive"))
      (node (ref "R5") (pin "1") (pinfunction "1_1") (pintype "passive"))
      (node (ref "U4") (pin "10") (pinfunction "VSW_10") (pintype "output"))
      (node (ref "U4") (pin "11") (pinfunction "VSW_11") (pintype "output"))
      (node (ref "U4") (pin "3") (pinfunction "VSW_3") (pintype "output"))
      (node (ref "U4") (pin "4") (pinfunction "VSW_4") (pintype "output"))
      (node (ref "U4") (pin "5") (pinfunction "VSW_5") (pintype "output"))
      (node (ref "U4") (pin "6") (pinfunction "VSW_6") (pintype "output"))
      (node (ref "U4") (pin "7") (pinfunction "VSW_7") (pintype "output"))
      (node (ref "U4") (pin "8") (pinfunction "VSW_8") (pintype "output"))
      (node (ref "U4") (pin "9") (pinfunction "VSW_9") (pintype "output"))
    )
    (net (code "29") (name "NFAULT") (class "Default")
      (node (ref "R23") (pin "1") (pinfunction "1_1") (pintype "passive"))
      (node (ref "R24") (pin "1") (pinfunction "1_1") (pintype "passive"))
      (node (ref "U1") (pin "28") (pinfunction "FAULT_N_28") (pintype "output"))
    )
    (net (code "30") (name "NRST") (class "Default")
      (node (ref "C24") (pin "1") (pinfunction "1_1") (pintype "passive"))
      (node (ref "IC1") (pin "7") (pinfunction "~{RST}_7") (pintype "input"))
      (node (ref "J1") (pin "10") (pinfunction "10_10") (pintype "bidirectional"))
      (node (ref "JP1") (pin "5") (pinfunction "5_5") (pintype "passive"))
      (node (ref "S2") (pin "3") (pinfunction "3_3") (pintype "passive"))
      (node (ref "S2") (pin "4") (pinfunction "4_4") (pintype "passive"))
    )
    (net (code "31") (name "NSCS{slash}GAIN") (class "Default")
      (node (ref "IC1") (pin "33") (pinfunction "PB12_33") (pintype "bidirectional"))
      (node (ref "U1") (pin "32") (pinfunction "SCS_N_32") (pintype "input"))
    )
    (net (code "32") (name "Net-(C17-Pad+)") (class "Default")
      (node (ref "C17") (pin "+") (pinfunction "+_+") (pintype "passive"))
      (node (ref "D2") (pin "A") (pinfunction "A_A") (pintype "passive"))
      (node (ref "U5") (pin "2") (pinfunction "OUT_2") (pintype "output"))
      (node (ref "U5") (pin "4") (pinfunction "OUT_4") (pintype "output"))
    )
    (net (code "33") (name "Net-(C18-Pad1)") (class "Default")
      (node (ref "C18") (pin "1") (pinfunction "1_1") (pintype "passive"))
      (node (ref "R10") (pin "2") (pinfunction "2_2") (pintype "passive"))
      (node (ref "Y1") (pin "4") (pinfunction "4_4") (pintype "passive"))
    )
    (net (code "34") (name "Net-(C19-Pad1)") (class "Default")
      (node (ref "C19") (pin "1") (pinfunction "1_1") (pintype "passive"))
      (node (ref "R11") (pin "2") (pinfunction "2_2") (pintype "passive"))
      (node (ref "Y1") (pin "1") (pinfunction "1_1") (pintype "passive"))
    )
    (net (code "35") (name "Net-(C20-Pad1)") (class "Default")
      (node (ref "C20") (pin "1") (pinfunction "1_1") (pintype "passive"))
      (node (ref "Q1") (pin "2") (pinfunction "2_2") (pintype "passive"))
      (node (ref "R12") (pin "2") (pinfunction "2_2") (pintype "passive"))
    )
    (net (code "36") (name "Net-(C21-Pad1)") (class "Default")
      (node (ref "C21") (pin "1") (pinfunction "1_1") (pintype "passive"))
      (node (ref "Q1") (pin "1") (pinfunction "1_1") (pintype "passive"))
      (node (ref "R13") (pin "2") (pinfunction "2_2") (pintype "passive"))
    )
    (net (code "37") (name "Net-(C23-Pad2)") (class "Default")
      (node (ref "C23") (pin "2") (pinfunction "2_2") (pintype "passive"))
      (node (ref "R15") (pin "1") (pinfunction "1_1") (pintype "passive"))
    )
    (net (code "38") (name "Net-(D1-K)") (class "Default")
      (node (ref "C10") (pin "1") (pinfunction "1_1") (pintype "passive"))
      (node (ref "D1") (pin "1") (pinfunction "K_1") (pintype "bidirectional"))
      (node (ref "L1") (pin "1") (pinfunction "1_1") (pintype "passive"))
      (node (ref "U1") (pin "44") (pinfunction "CB_44") (pintype "power_in"))
    )
    (net (code "39") (name "Net-(IC1-PC13)") (class "Default")
      (node (ref "C23") (pin "1") (pinfunction "1_1") (pintype "passive"))
      (node (ref "IC1") (pin "2") (pinfunction "PC13_2") (pintype "bidirectional"))
      (node (ref "R14") (pin "1") (pinfunction "1_1") (pintype "passive"))
      (node (ref "S1") (pin "1") (pinfunction "1_1") (pintype "passive"))
      (node (ref "S1") (pin "2") (pinfunction "2_2") (pintype "passive"))
    )
    (net (code "40") (name "Net-(IC1-PF0)") (class "Default")
      (node (ref "IC1") (pin "5") (pinfunction "PF0_5") (pintype "bidirectional"))
      (node (ref "R12") (pin "1") (pinfunction "1_1") (pintype "passive"))
    )
    (net (code "41") (name "Net-(IC1-PF1)") (class "Default")
      (node (ref "IC1") (pin "6") (pinfunction "PF1_6") (pintype "bidirectional"))
      (node (ref "R13") (pin "1") (pinfunction "1_1") (pintype "passive"))
    )
    (net (code "42") (name "Net-(LED1-PadA)") (class "Default")
      (node (ref "LED1") (pin "A") (pinfunction "A_A") (pintype "passive"))
      (node (ref "R9") (pin "1") (pinfunction "1_1") (pintype "passive"))
    )
    (net (code "43") (name "Net-(LED2-PadC)") (class "Default")
      (node (ref "LED2") (pin "C") (pinfunction "C_C") (pintype "passive"))
      (node (ref "R24") (pin "2") (pinfunction "2_2") (pintype "passive"))
    )
    (net (code "44") (name "Net-(U1-CPH)") (class "Default")
      (node (ref "C9") (pin "1") (pinfunction "1_1") (pintype "passive"))
      (node (ref "U1") (pin "4") (pinfunction "CPH_4") (pintype "passive"))
    )
    (net (code "45") (name "Net-(U1-CPL)") (class "Default")
      (node (ref "C9") (pin "2") (pinfunction "2_2") (pintype "passive"))
      (node (ref "U1") (pin "3") (pinfunction "CPL_3") (pintype "passive"))
    )
    (net (code "46") (name "Net-(U1-DVDD)") (class "Default")
      (node (ref "C36") (pin "1") (pinfunction "1_1") (pintype "passive"))
      (node (ref "U1") (pin "36") (pinfunction "DVDD_36") (pintype "power_in"))
    )
    (net (code "47") (name "Net-(U1-FB)") (class "Default")
      (node (ref "R7") (pin "1") (pinfunction "1_1") (pintype "passive"))
      (node (ref "R8") (pin "2") (pinfunction "2_2") (pintype "passive"))
      (node (ref "U1") (pin "1") (pinfunction "FB_1") (pintype "input"))
    )
    (net (code "48") (name "Net-(U1-SW)") (class "Default")
      (node (ref "C10") (pin "2") (pinfunction "2_2") (pintype "passive"))
      (node (ref "U1") (pin "45") (pinfunction "SW_45") (pintype "output"))
    )
    (net (code "49") (name "Net-(U1-VCP)") (class "Default")
      (node (ref "C7") (pin "2") (pinfunction "2_2") (pintype "passive"))
      (node (ref "U1") (pin "5") (pinfunction "VCP_5") (pintype "power_in"))
    )
    (net (code "50") (name "PA2") (class "Default")
      (node (ref "IC1") (pin "16") (pinfunction "PA2_16") (pintype "bidirectional"))
      (node (ref "JP5") (pin "1") (pinfunction "1_1") (pintype "passive"))
    )
    (net (code "51") (name "PA3") (class "Default")
      (node (ref "IC1") (pin "17") (pinfunction "PA3_17") (pintype "bidirectional"))
      (node (ref "JP5") (pin "2") (pinfunction "2_2") (pintype "passive"))
    )
    (net (code "52") (name "PC14") (class "Default")
      (node (ref "IC1") (pin "3") (pinfunction "PC14_3") (pintype "bidirectional"))
      (node (ref "R10") (pin "1") (pinfunction "1_1") (pintype "passive"))
    )
    (net (code "53") (name "PC15") (class "Default")
      (node (ref "IC1") (pin "4") (pinfunction "PC15_4") (pintype "bidirectional"))
      (node (ref "R11") (pin "1") (pinfunction "1_1") (pintype "passive"))
    )
    (net (code "54") (name "RGND1") (class "Default")
      (node (ref "C3") (pin "2") (pinfunction "2_2") (pintype "passive"))
      (node (ref "R25") (pin "1") (pinfunction "1_1") (pintype "passive"))
      (node (ref "U1") (pin "11") (pinfunction "SPA_11") (pintype "input"))
      (node (ref "U2") (pin "12") (pinfunction "PGND_12") (pintype "power_in"))
      (node (ref "U2") (pin "13") (pinfunction "PGND_13") (pintype "power_in"))
      (node (ref "U2") (pin "14") (pinfunction "PGND_14") (pintype "power_in"))
      (node (ref "U2") (pin "15") (pinfunction "PGND_15") (pintype "power_in"))
      (node (ref "U2") (pin "16") (pinfunction "PGND_16") (pintype "power_in"))
      (node (ref "U2") (pin "17") (pinfunction "PGND_17") (pintype "power_in"))
      (node (ref "U2") (pin "18") (pinfunction "PGND_18") (pintype "power_in"))
      (node (ref "U2") (pin "19") (pinfunction "PGND_19") (pintype "power_in"))
      (node (ref "U2") (pin "20") (pinfunction "PGND_20") (pintype "power_in"))
    )
    (net (code "55") (name "RGND2") (class "Default")
      (node (ref "C4") (pin "1") (pinfunction "1_1") (pintype "passive"))
      (node (ref "R26") (pin "1") (pinfunction "1_1") (pintype "passive"))
      (node (ref "U1") (pin "14") (pinfunction "SPB_14") (pintype "input"))
      (node (ref "U3") (pin "12") (pinfunction "PGND_12") (pintype "power_in"))
      (node (ref "U3") (pin "13") (pinfunction "PGND_13") (pintype "power_in"))
      (node (ref "U3") (pin "14") (pinfunction "PGND_14") (pintype "power_in"))
      (node (ref "U3") (pin "15") (pinfunction "PGND_15") (pintype "power_in"))
      (node (ref "U3") (pin "16") (pinfunction "PGND_16") (pintype "power_in"))
      (node (ref "U3") (pin "17") (pinfunction "PGND_17") (pintype "power_in"))
      (node (ref "U3") (pin "18") (pinfunction "PGND_18") (pintype "power_in"))
      (node (ref "U3") (pin "19") (pinfunction "PGND_19") (pintype "power_in"))
      (node (ref "U3") (pin "20") (pinfunction "PGND_20") (pintype "power_in"))
    )
    (net (code "56") (name "RGND3") (class "Default")
      (node (ref "C5") (pin "2") (pinfunction "2_2") (pintype "passive"))
      (node (ref "R27") (pin "1") (pinfunction "1_1") (pintype "passive"))
      (node (ref "U1") (pin "21") (pinfunction "SPC_21") (pintype "input"))
      (node (ref "U4") (pin "12") (pinfunction "PGND_12") (pintype "power_in"))
      (node (ref "U4") (pin "13") (pinfunction "PGND_13") (pintype "power_in"))
      (node (ref "U4") (pin "14") (pinfunction "PGND_14") (pintype "power_in"))
      (node (ref "U4") (pin "15") (pinfunction "PGND_15") (pintype "power_in"))
      (node (ref "U4") (pin "16") (pinfunction "PGND_16") (pintype "power_in"))
      (node (ref "U4") (pin "17") (pinfunction "PGND_17") (pintype "power_in"))
      (node (ref "U4") (pin "18") (pinfunction "PGND_18") (pintype "power_in"))
      (node (ref "U4") (pin "19") (pinfunction "PGND_19") (pintype "power_in"))
      (node (ref "U4") (pin "20") (pinfunction "PGND_20") (pintype "power_in"))
    )
    (net (code "57") (name "SCLK") (class "Default")
      (node (ref "IC1") (pin "34") (pinfunction "PB13_34") (pintype "bidirectional"))
      (node (ref "U1") (pin "31") (pinfunction "SCLK_31") (pintype "input"))
    )
    (net (code "58") (name "SDI") (class "Default")
      (node (ref "IC1") (pin "36") (pinfunction "PB15_36") (pintype "bidirectional"))
      (node (ref "U1") (pin "30") (pinfunction "SDI_30") (pintype "input"))
    )
    (net (code "59") (name "SDO") (class "Default")
      (node (ref "IC1") (pin "35") (pinfunction "PB14_35") (pintype "bidirectional"))
      (node (ref "R20") (pin "1") (pinfunction "1_1") (pintype "passive"))
      (node (ref "U1") (pin "29") (pinfunction "SDO_29") (pintype "output"))
    )
    (net (code "60") (name "SHA") (class "Default")
      (node (ref "U1") (pin "9") (pinfunction "SHA_9") (pintype "input"))
      (node (ref "U2") (pin "2") (pinfunction "SH_2") (pintype "input"))
    )
    (net (code "61") (name "SHB") (class "Default")
      (node (ref "U1") (pin "16") (pinfunction "SHB_16") (pintype "input"))
      (node (ref "U3") (pin "2") (pinfunction "SH_2") (pintype "input"))
    )
    (net (code "62") (name "SHC") (class "Default")
      (node (ref "U1") (pin "19") (pinfunction "SHC_19") (pintype "input"))
      (node (ref "U4") (pin "2") (pinfunction "SH_2") (pintype "input"))
    )
    (net (code "63") (name "SOA") (class "Default")
      (node (ref "R17") (pin "2") (pinfunction "2_2") (pintype "passive"))
      (node (ref "U1") (pin "25") (pinfunction "SOA_25") (pintype "output"))
    )
    (net (code "64") (name "SOB") (class "Default")
      (node (ref "R18") (pin "2") (pinfunction "2_2") (pintype "passive"))
      (node (ref "U1") (pin "24") (pinfunction "SOB_24") (pintype "output"))
    )
    (net (code "65") (name "SOC") (class "Default")
      (node (ref "R19") (pin "2") (pinfunction "2_2") (pintype "passive"))
      (node (ref "U1") (pin "23") (pinfunction "SOC_23") (pintype "output"))
    )
    (net (code "66") (name "SWCLK") (class "Default")
      (node (ref "IC1") (pin "49") (pinfunction "PA14_49") (pintype "bidirectional"))
      (node (ref "J1") (pin "4") (pinfunction "4_4") (pintype "bidirectional"))
      (node (ref "JP1") (pin "2") (pinfunction "2_2") (pintype "passive"))
    )
    (net (code "67") (name "SWDIO") (class "Default")
      (node (ref "IC1") (pin "46") (pinfunction "PA13_46") (pintype "bidirectional"))
      (node (ref "J1") (pin "2") (pinfunction "2_2") (pintype "bidirectional"))
      (node (ref "JP1") (pin "4") (pinfunction "4_4") (pintype "passive"))
    )
    (net (code "68") (name "SWO") (class "Default")
      (node (ref "IC1") (pin "55") (pinfunction "PB3_55") (pintype "bidirectional"))
      (node (ref "J1") (pin "6") (pinfunction "6_6") (pintype "bidirectional"))
      (node (ref "JP1") (pin "6") (pinfunction "6_6") (pintype "passive"))
    )
    (net (code "69") (name "VBAT") (class "Default")
      (node (ref "C22") (pin "2") (pinfunction "2_2") (pintype "passive"))
      (node (ref "IC1") (pin "1") (pinfunction "VBAT_1") (pintype "power_in"))
    )
    (net (code "70") (name "VIN") (class "Default")
      (node (ref "C16") (pin "+") (pinfunction "+_+") (pintype "passive"))
      (node (ref "INPUT") (pin "1") (pinfunction "KL_1") (pintype "passive"))
      (node (ref "U5") (pin "3") (pinfunction "IN_3") (pintype "input"))
    )
    (net (code "71") (name "VM") (class "Default")
      (node (ref "C2") (pin "1") (pinfunction "1_1") (pintype "passive"))
      (node (ref "C3") (pin "1") (pinfunction "1_1") (pintype "passive"))
      (node (ref "C33") (pin "+") (pinfunction "+_+") (pintype "passive"))
      (node (ref "C34") (pin "+") (pinfunction "+_+") (pintype "passive"))
      (node (ref "C4") (pin "2") (pinfunction "2_2") (pintype "passive"))
      (node (ref "C5") (pin "1") (pinfunction "1_1") (pintype "passive"))
      (node (ref "C6") (pin "1") (pinfunction "1_1") (pintype "passive"))
      (node (ref "C7") (pin "1") (pinfunction "1_1") (pintype "passive"))
      (node (ref "C8") (pin "1") (pinfunction "1_1") (pintype "passive"))
      (node (ref "JP2") (pin "1") (pinfunction "1_1") (pintype "passive"))
      (node (ref "R22") (pin "2") (pinfunction "2_2") (pintype "passive"))
      (node (ref "U1") (pin "47") (pinfunction "VIN_47") (pintype "power_in"))
      (node (ref "U1") (pin "48") (pinfunction "SHDN_N_48") (pintype "input"))
      (node (ref "U1") (pin "6") (pinfunction "VM_6") (pintype "power_in"))
      (node (ref "U1") (pin "7") (pinfunction "VDRAIN_7") (pintype "input"))
      (node (ref "U2") (pin "27") (pinfunction "VIN_27") (pintype "input"))
      (node (ref "U3") (pin "27") (pinfunction "VIN_27") (pintype "input"))
      (node (ref "U4") (pin "27") (pinfunction "VIN_27") (pintype "input"))
    )
    (net (code "72") (name "VSENA") (class "Default")
      (node (ref "R3") (pin "2") (pinfunction "2_2") (pintype "passive"))
      (node (ref "R4") (pin "1") (pinfunction "1_1") (pintype "passive"))
      (node (ref "U$1") (pin "D1+") (pinfunction "D1+_D1+") (pintype "passive"))
    )
    (net (code "73") (name "VSENB") (class "Default")
      (node (ref "R1") (pin "2") (pinfunction "2_2") (pintype "passive"))
      (node (ref "R2") (pin "1") (pinfunction "1_1") (pintype "passive"))
      (node (ref "U$1") (pin "D2+") (pinfunction "D2+_D2+") (pintype "passive"))
    )
    (net (code "74") (name "VSENC") (class "Default")
      (node (ref "R5") (pin "2") (pinfunction "2_2") (pintype "passive"))
      (node (ref "R6") (pin "1") (pinfunction "1_1") (pintype "passive"))
      (node (ref "U$1") (pin "D2-") (pinfunction "D2-_D2-") (pintype "passive"))
    )
    (net (code "75") (name "VSENVM") (class "Default")
      (node (ref "C35") (pin "1") (pinfunction "1_1") (pintype "passive"))
      (node (ref "IC1") (pin "15") (pinfunction "PA1_15") (pintype "bidirectional"))
      (node (ref "R21") (pin "2") (pinfunction "2_2") (pintype "passive"))
      (node (ref "R22") (pin "1") (pinfunction "1_1") (pintype "passive"))
      (node (ref "U$1") (pin "D1-") (pinfunction "D1-_D1-") (pintype "passive"))
    )
    (net (code "76") (name "unconnected-(IC1-PA4-Pad20)") (class "Default")
      (node (ref "IC1") (pin "20") (pinfunction "PA4_20") (pintype "bidirectional"))
    )
    (net (code "77") (name "unconnected-(IC1-PA5-Pad21)") (class "Default")
      (node (ref "IC1") (pin "21") (pinfunction "PA5_21") (pintype "bidirectional"))
    )
    (net (code "78") (name "unconnected-(IC1-PA6-Pad22)") (class "Default")
      (node (ref "IC1") (pin "22") (pinfunction "PA6_22") (pintype "bidirectional"))
    )
    (net (code "79") (name "unconnected-(IC1-PA11-Pad44)") (class "Default")
      (node (ref "IC1") (pin "44") (pinfunction "PA11_44") (pintype "bidirectional"))
    )
    (net (code "80") (name "unconnected-(IC1-PA12-Pad45)") (class "Default")
      (node (ref "IC1") (pin "45") (pinfunction "PA12_45") (pintype "bidirectional"))
    )
    (net (code "81") (name "unconnected-(IC1-PA15-Pad50)") (class "Default")
      (node (ref "IC1") (pin "50") (pinfunction "PA15_50") (pintype "bidirectional"))
    )
    (net (code "82") (name "unconnected-(IC1-PB2-Pad28)") (class "Default")
      (node (ref "IC1") (pin "28") (pinfunction "PB2_28") (pintype "bidirectional"))
    )
    (net (code "83") (name "unconnected-(IC1-PB4-Pad56)") (class "Default")
      (node (ref "IC1") (pin "56") (pinfunction "PB4_56") (pintype "bidirectional"))
    )
    (net (code "84") (name "unconnected-(IC1-PB5-Pad57)") (class "Default")
      (node (ref "IC1") (pin "57") (pinfunction "PB5_57") (pintype "bidirectional"))
    )
    (net (code "85") (name "unconnected-(IC1-PB6-Pad58)") (class "Default")
      (node (ref "IC1") (pin "58") (pinfunction "PB6_58") (pintype "bidirectional"))
    )
    (net (code "86") (name "unconnected-(IC1-PB7-Pad59)") (class "Default")
      (node (ref "IC1") (pin "59") (pinfunction "PB7_59") (pintype "bidirectional"))
    )
    (net (code "87") (name "unconnected-(IC1-PB8-Pad61)") (class "Default")
      (node (ref "IC1") (pin "61") (pinfunction "PB8_61") (pintype "bidirectional"))
    )
    (net (code "88") (name "unconnected-(IC1-PB9-Pad62)") (class "Default")
      (node (ref "IC1") (pin "62") (pinfunction "PB9_62") (pintype "bidirectional"))
    )
    (net (code "89") (name "unconnected-(IC1-PB10-Pad29)") (class "Default")
      (node (ref "IC1") (pin "29") (pinfunction "PB10_29") (pintype "bidirectional"))
    )
    (net (code "90") (name "unconnected-(IC1-PB11-Pad30)") (class "Default")
      (node (ref "IC1") (pin "30") (pinfunction "PB11_30") (pintype "bidirectional"))
    )
    (net (code "91") (name "unconnected-(IC1-PC2-Pad10)") (class "Default")
      (node (ref "IC1") (pin "10") (pinfunction "PC2_10") (pintype "bidirectional"))
    )
    (net (code "92") (name "unconnected-(IC1-PC3-Pad11)") (class "Default")
      (node (ref "IC1") (pin "11") (pinfunction "PC3_11") (pintype "bidirectional"))
    )
    (net (code "93") (name "unconnected-(IC1-PC5-Pad25)") (class "Default")
      (node (ref "IC1") (pin "25") (pinfunction "PC5_25") (pintype "bidirectional"))
    )
    (net (code "94") (name "unconnected-(IC1-PC6-Pad37)") (class "Default")
      (node (ref "IC1") (pin "37") (pinfunction "PC6_37") (pintype "bidirectional"))
    )
    (net (code "95") (name "unconnected-(IC1-PC7-Pad38)") (class "Default")
      (node (ref "IC1") (pin "38") (pinfunction "PC7_38") (pintype "bidirectional"))
    )
    (net (code "96") (name "unconnected-(IC1-PC8-Pad39)") (class "Default")
      (node (ref "IC1") (pin "39") (pinfunction "PC8_39") (pintype "bidirectional"))
    )
    (net (code "97") (name "unconnected-(IC1-PC9-Pad40)") (class "Default")
      (node (ref "IC1") (pin "40") (pinfunction "PC9_40") (pintype "bidirectional"))
    )
    (net (code "98") (name "unconnected-(IC1-VSS_1-Pad63)") (class "Default")
      (node (ref "IC1") (pin "63") (pinfunction "VSS_1_63") (pintype "passive"))
    )
    (net (code "99") (name "unconnected-(IC1-VSS_2-Pad31)") (class "Default")
      (node (ref "IC1") (pin "31") (pinfunction "VSS_2_31") (pintype "passive"))
    )
    (net (code "100") (name "unconnected-(IC1-VSS_3-Pad47)") (class "Default")
      (node (ref "IC1") (pin "47") (pinfunction "VSS_3_47") (pintype "passive"))
    )
    (net (code "101") (name "unconnected-(IC1-VSS_4-Pad18)") (class "Default")
      (node (ref "IC1") (pin "18") (pinfunction "VSS_4_18") (pintype "passive"))
    )
    (net (code "102") (name "unconnected-(J1-Pad3)") (class "Default")
      (node (ref "J1") (pin "3") (pinfunction "3_3") (pintype "bidirectional"))
    )
    (net (code "103") (name "unconnected-(J1-Pad8)") (class "Default")
      (node (ref "J1") (pin "8") (pinfunction "8_8") (pintype "bidirectional"))
    )
    (net (code "104") (name "unconnected-(U1-CAL-Pad34)") (class "Default")
      (node (ref "U1") (pin "34") (pinfunction "CAL_34") (pintype "input"))
    )
    (net (code "105") (name "unconnected-(U1-NC-Pad46)") (class "Default")
      (node (ref "U1") (pin "46") (pinfunction "NC_46") (pintype "no_connect"))
    )
    (net (code "106") (name "unconnected-(U6-PG-Pad3)") (class "Default")
      (node (ref "U6") (pin "3") (pinfunction "PG_3") (pintype "bidirectional"))
    )
  )
)
